# 111.net
KiCad netlist of a schematic drawn in Altium Designer
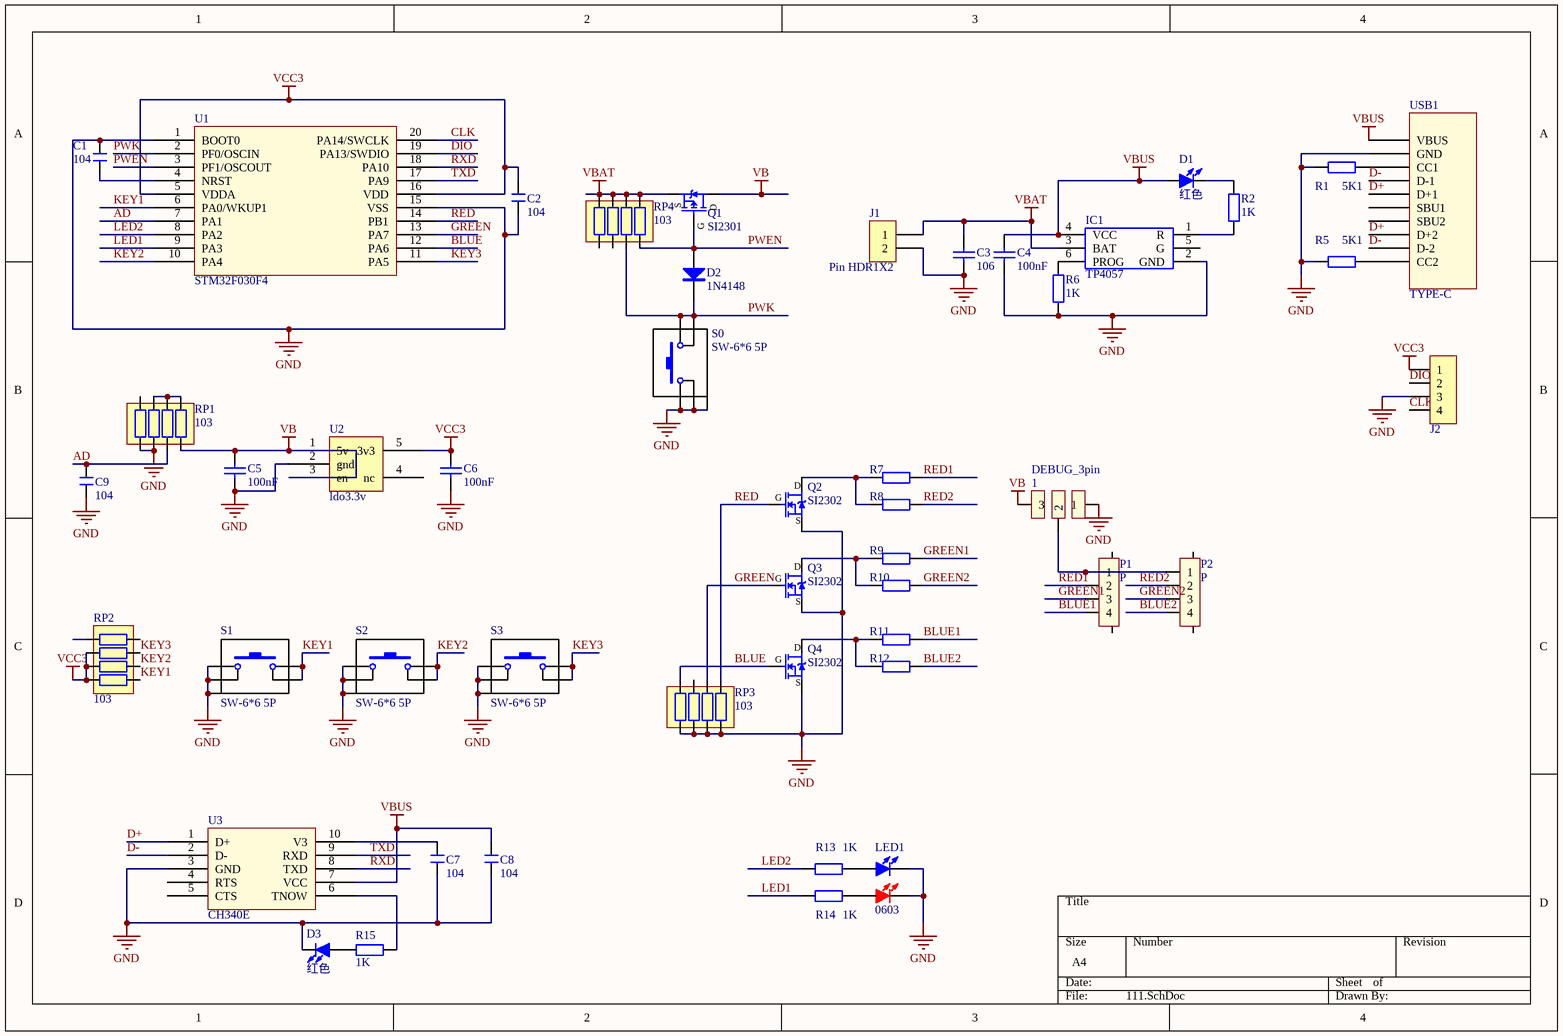
[diagram p0: 111.SchDoc]

(export (version "E")
  (design (tool "Eeschema 10.0.6"))
  (components
    (comp (ref "1") (value "DEBUG_3pin") (footprint "DEBUG_3pim") (libsource (lib "0") (part "DEBUG_3pin")))
    (comp (ref "C1")
      (value "104")
      (footprint "C 0402_M")
      (description "无极性贴片电容")
      (libsource (lib "3.1   - 电阻-电容-电感") (part "C"))
    )
    (comp (ref "C2")
      (value "104")
      (footprint "C 0402_M")
      (description "无极性贴片电容")
      (libsource (lib "3.1   - 电阻-电容-电感") (part "C"))
    )
    (comp (ref "C3")
      (value "106")
      (footprint "C-RAD-0805")
      (description "无极性电容")
      (fields (field (name "Comment") "Cap") (field (name "PUBLISHER") "Altium Limited"))
      (libsource (lib "fszhang") (part "Cap"))
    )
    (comp (ref "C4")
      (value "100nF")
      (footprint "C-RAD-0603")
      (description "无极性电容")
      (fields (field (name "Comment") "Cap") (field (name "PUBLISHER") "Altium Limited"))
      (libsource (lib "fszhang") (part "Cap"))
    )
    (comp (ref "C5")
      (value "100nF")
      (footprint "C-RAD-0603")
      (description "无极性电容")
      (fields (field (name "Comment") "Cap") (field (name "PUBLISHER") "Altium Limited"))
      (libsource (lib "fszhang") (part "Cap"))
    )
    (comp (ref "C6")
      (value "100nF")
      (footprint "C-RAD-0603")
      (description "无极性电容")
      (fields (field (name "Comment") "Cap") (field (name "PUBLISHER") "Altium Limited"))
      (libsource (lib "fszhang") (part "Cap"))
    )
    (comp (ref "C7")
      (value "104")
      (footprint "C 0402_M")
      (description "无极性贴片电容")
      (libsource (lib "3.1   - 电阻-电容-电感") (part "C"))
    )
    (comp (ref "C8")
      (value "104")
      (footprint "C 0402_M")
      (description "无极性贴片电容")
      (libsource (lib "3.1   - 电阻-电容-电感") (part "C"))
    )
    (comp (ref "C9")
      (value "104")
      (footprint "C 0402_M")
      (description "无极性贴片电容")
      (libsource (lib "3.1   - 电阻-电容-电感") (part "C"))
    )
    (comp (ref "D1")
      (value "红色")
      (footprint "LED 0603R")
      (description "贴片LED")
      (libsource (lib "9.1   - LED") (part "LED-SMD"))
    )
    (comp (ref "D2")
      (value "1N4148")
      (footprint "SOD-323")
      (description "高速开关二极管")
      (libsource (lib "8.1   - 二极管-整流桥") (part "1N4148"))
    )
    (comp (ref "D3")
      (value "红色")
      (footprint "LED 0603R")
      (description "贴片LED")
      (libsource (lib "9.1   - LED") (part "LED-SMD"))
    )
    (comp (ref "IC1") (value "TP4057") (footprint "SOT23-6M") (libsource (lib "常用") (part "TP4057")))
    (comp (ref "J1")
      (value "Pin HDR1X2")
      (footprint "Pin HDR1X2/2.54mm-S")
      (libsource (lib "排针") (part "Pin HDR1X2"))
    )
    (comp (ref "J2")
      (value "HDR-1X4")
      (footprint "HDR2.0-LI-4P")
      (description "4P接插件")
      (libsource (lib "4.5   - 接插件-脚距2.0") (part "Header 4"))
    )
    (comp (ref "LED1")
      (value "0603")
      (footprint "LED 0603-RG")
      (description "贴片双色LED")
      (libsource (lib "9.1   - LED") (part "LED-SMD-RG"))
    )
    (comp (ref "P1") (value "P") (footprint "SH1.0_4pin") (libsource (lib "0") (part "SH1.0-4")))
    (comp (ref "P2") (value "P") (footprint "SH1.0_4pin") (libsource (lib "0") (part "SH1.0-4")))
    (comp (ref "Q1")
      (value "SI2301")
      (footprint "SOT23-3N")
      (description "P沟道 20V/2.8A")
      (libsource (lib "6.1   - 场效应管-可控硅") (part "SI2301"))
    )
    (comp (ref "Q2")
      (value "SI2302")
      (footprint "SOT23-3N")
      (description "N沟道 20V/3A")
      (libsource (lib "6.1   - 场效应管-可控硅") (part "SI2302"))
    )
    (comp (ref "Q3")
      (value "SI2302")
      (footprint "SOT23-3N")
      (description "N沟道 20V/3A")
      (libsource (lib "6.1   - 场效应管-可控硅") (part "SI2302"))
    )
    (comp (ref "Q4")
      (value "SI2302")
      (footprint "SOT23-3N")
      (description "N沟道 20V/3A")
      (libsource (lib "6.1   - 场效应管-可控硅") (part "SI2302"))
    )
    (comp (ref "R1")
      (value "5K1")
      (footprint "R 0402_M")
      (description "贴片电阻")
      (libsource (lib "3.1   - 电阻-电容-电感") (part "R"))
    )
    (comp (ref "R2")
      (value "1K")
      (footprint "R 0402_M")
      (description "贴片电阻")
      (libsource (lib "3.1   - 电阻-电容-电感") (part "R"))
    )
    (comp (ref "R5")
      (value "5K1")
      (footprint "R 0402_M")
      (description "贴片电阻")
      (libsource (lib "3.1   - 电阻-电容-电感") (part "R"))
    )
    (comp (ref "R6")
      (value "1K")
      (footprint "R 0402_M")
      (description "贴片电阻")
      (libsource (lib "3.1   - 电阻-电容-电感") (part "R"))
    )
    (comp (ref "R7")
      (value "Res1")
      (footprint "0603-1")
      (description "贴片电阻")
      (fields (field (name "PUBLISHER") "Altium Limited"))
      (libsource (lib "fszhang") (part "Res1"))
    )
    (comp (ref "R8")
      (value "Res1")
      (footprint "0603-1")
      (description "贴片电阻")
      (fields (field (name "PUBLISHER") "Altium Limited"))
      (libsource (lib "fszhang") (part "Res1"))
    )
    (comp (ref "R9")
      (value "Res1")
      (footprint "0603-1")
      (description "贴片电阻")
      (fields (field (name "PUBLISHER") "Altium Limited"))
      (libsource (lib "fszhang") (part "Res1"))
    )
    (comp (ref "R10")
      (value "Res1")
      (footprint "0603-1")
      (description "贴片电阻")
      (fields (field (name "PUBLISHER") "Altium Limited"))
      (libsource (lib "fszhang") (part "Res1"))
    )
    (comp (ref "R11")
      (value "Res1")
      (footprint "0603-1")
      (description "贴片电阻")
      (fields (field (name "PUBLISHER") "Altium Limited"))
      (libsource (lib "fszhang") (part "Res1"))
    )
    (comp (ref "R12")
      (value "Res1")
      (footprint "0603-1")
      (description "贴片电阻")
      (fields (field (name "PUBLISHER") "Altium Limited"))
      (libsource (lib "fszhang") (part "Res1"))
    )
    (comp (ref "R13")
      (value "1K")
      (footprint "R 0402_M")
      (description "贴片电阻")
      (libsource (lib "3.1   - 电阻-电容-电感") (part "R"))
    )
    (comp (ref "R14")
      (value "1K")
      (footprint "R 0402_M")
      (description "贴片电阻")
      (libsource (lib "3.1   - 电阻-电容-电感") (part "R"))
    )
    (comp (ref "R15")
      (value "1K")
      (footprint "R 0402_M")
      (description "贴片电阻")
      (libsource (lib "3.1   - 电阻-电容-电感") (part "R"))
    )
    (comp (ref "RP1")
      (value "103")
      (footprint "RCA-8P4R-0402")
      (description "贴片网络排阻")
      (libsource (lib "3.1   - 电阻-电容-电感") (part "R-8P4R"))
    )
    (comp (ref "RP2")
      (value "103")
      (footprint "RCA-8P4R-0402")
      (description "贴片网络排阻")
      (libsource (lib "") (part "R-8P4R_1"))
    )
    (comp (ref "RP3")
      (value "103")
      (footprint "RCA-8P4R-0402")
      (description "贴片网络排阻")
      (libsource (lib "3.1   - 电阻-电容-电感") (part "R-8P4R"))
    )
    (comp (ref "RP4")
      (value "103")
      (footprint "RCA-8P4R-0402")
      (description "贴片网络排阻")
      (libsource (lib "3.1   - 电阻-电容-电感") (part "R-8P4R"))
    )
    (comp (ref "S0")
      (value "SW-6*6 5P")
      (footprint "SW6*6")
      (description "微动开关")
      (fields (field (name "PUBLISHER") "Altium Limited"))
      (libsource (lib "fszhang") (part "SW-6*6 5P"))
    )
    (comp (ref "S1")
      (value "SW-6*6 5P")
      (footprint "SW6*6")
      (description "微动开关")
      (fields (field (name "PUBLISHER") "Altium Limited"))
      (libsource (lib "fszhang") (part "SW-6*6 5P"))
    )
    (comp (ref "S2")
      (value "SW-6*6 5P")
      (footprint "SW6*6")
      (description "微动开关")
      (fields (field (name "PUBLISHER") "Altium Limited"))
      (libsource (lib "fszhang") (part "SW-6*6 5P"))
    )
    (comp (ref "S3")
      (value "SW-6*6 5P")
      (footprint "SW6*6")
      (description "微动开关")
      (fields (field (name "PUBLISHER") "Altium Limited"))
      (libsource (lib "fszhang") (part "SW-6*6 5P"))
    )
    (comp (ref "U1")
      (value "STM32F030F4")
      (footprint "TSSOP20")
      (libsource (lib "fszhang") (part "STM32F030F4"))
    )
    (comp (ref "U2") (value "ldo3.3v") (footprint "SOT23-5") (libsource (lib "3.3ldo") (part "Component_1")))
    (comp (ref "U3") (value "CH340E") (footprint "MSOP10_M") (libsource (lib "1") (part "CH340E")))
    (comp (ref "USB1") (value "TYPE-C") (footprint "TYPE-C") (libsource (lib "1") (part "USB-C")))
  )
  (nets
    (net (code "1") (name "/AD") (class "Default")
      (node (ref "C9") (pin "2") (pinfunction "2_2") (pintype "passive"))
      (node (ref "RP1") (pin "3") (pinfunction "3_3") (pintype "passive"))
      (node (ref "U1") (pin "7") (pinfunction "PA1_7") (pintype "passive"))
    )
    (net (code "2") (name "/BLUE") (class "Default")
      (node (ref "Q4") (pin "1") (pinfunction "G_1") (pintype "passive"))
      (node (ref "RP3") (pin "8") (pinfunction "8_8") (pintype "passive"))
      (node (ref "U1") (pin "12") (pinfunction "PA6_12") (pintype "passive"))
    )
    (net (code "3") (name "/BLUE1") (class "Default")
      (node (ref "P1") (pin "4") (pinfunction "4_4") (pintype "passive"))
      (node (ref "R11") (pin "2") (pinfunction "2_2") (pintype "passive"))
    )
    (net (code "4") (name "/BLUE2") (class "Default")
      (node (ref "P2") (pin "4") (pinfunction "4_4") (pintype "passive"))
      (node (ref "R12") (pin "2") (pinfunction "2_2") (pintype "passive"))
    )
    (net (code "5") (name "/CLK") (class "Default")
      (node (ref "J2") (pin "4") (pinfunction "4_4") (pintype "passive"))
      (node (ref "U1") (pin "20") (pinfunction "PA14/SWCLK_20") (pintype "passive"))
    )
    (net (code "6") (name "/D+") (class "Default")
      (node (ref "U3") (pin "1") (pinfunction "D+_1") (pintype "passive"))
      (node (ref "USB1") (pin "D+1") (pinfunction "D+1_D+1") (pintype "passive"))
      (node (ref "USB1") (pin "D+2") (pinfunction "D+2_D+2") (pintype "passive"))
    )
    (net (code "7") (name "/D-") (class "Default")
      (node (ref "U3") (pin "2") (pinfunction "D-_2") (pintype "passive"))
      (node (ref "USB1") (pin "D-1") (pinfunction "D-1_D-1") (pintype "passive"))
      (node (ref "USB1") (pin "D-2") (pinfunction "D-2_D-2") (pintype "passive"))
    )
    (net (code "8") (name "/DIO") (class "Default")
      (node (ref "J2") (pin "2") (pinfunction "2_2") (pintype "passive"))
      (node (ref "U1") (pin "19") (pinfunction "PA13/SWDIO_19") (pintype "passive"))
    )
    (net (code "9") (name "/GREEN") (class "Default")
      (node (ref "Q3") (pin "1") (pinfunction "G_1") (pintype "passive"))
      (node (ref "RP3") (pin "6") (pinfunction "6_6") (pintype "passive"))
      (node (ref "U1") (pin "13") (pinfunction "PA7_13") (pintype "passive"))
    )
    (net (code "10") (name "/GREEN1") (class "Default")
      (node (ref "P1") (pin "3") (pinfunction "3_3") (pintype "passive"))
      (node (ref "R9") (pin "2") (pinfunction "2_2") (pintype "passive"))
    )
    (net (code "11") (name "/GREEN2") (class "Default")
      (node (ref "P2") (pin "3") (pinfunction "3_3") (pintype "passive"))
      (node (ref "R10") (pin "2") (pinfunction "2_2") (pintype "passive"))
    )
    (net (code "12") (name "/KEY1") (class "Default")
      (node (ref "RP2") (pin "1") (pinfunction "1_1") (pintype "passive"))
      (node (ref "S1") (pin "2") (pinfunction "2_2") (pintype "passive"))
      (node (ref "S1") (pin "3") (pinfunction "3_3") (pintype "passive"))
      (node (ref "U1") (pin "6") (pinfunction "PA0/WKUP1_6") (pintype "passive"))
    )
    (net (code "13") (name "/KEY2") (class "Default")
      (node (ref "RP2") (pin "2") (pinfunction "2_2") (pintype "passive"))
      (node (ref "S2") (pin "2") (pinfunction "2_2") (pintype "passive"))
      (node (ref "S2") (pin "3") (pinfunction "3_3") (pintype "passive"))
      (node (ref "U1") (pin "10") (pinfunction "PA4_10") (pintype "passive"))
    )
    (net (code "14") (name "/KEY3") (class "Default")
      (node (ref "RP2") (pin "3") (pinfunction "3_3") (pintype "passive"))
      (node (ref "S3") (pin "2") (pinfunction "2_2") (pintype "passive"))
      (node (ref "S3") (pin "3") (pinfunction "3_3") (pintype "passive"))
      (node (ref "U1") (pin "11") (pinfunction "PA5_11") (pintype "passive"))
    )
    (net (code "15") (name "/LED1") (class "Default")
      (node (ref "R14") (pin "1") (pinfunction "1_1") (pintype "passive"))
      (node (ref "U1") (pin "9") (pinfunction "PA3_9") (pintype "passive"))
    )
    (net (code "16") (name "/LED2") (class "Default")
      (node (ref "R13") (pin "1") (pinfunction "1_1") (pintype "passive"))
      (node (ref "U1") (pin "8") (pinfunction "PA2_8") (pintype "passive"))
    )
    (net (code "17") (name "/PWEN") (class "Default")
      (node (ref "D2") (pin "A") (pinfunction "A_A") (pintype "passive"))
      (node (ref "Q1") (pin "1") (pinfunction "G_1") (pintype "passive"))
      (node (ref "RP4") (pin "4") (pinfunction "4_4") (pintype "passive"))
      (node (ref "U1") (pin "3") (pinfunction "PF1/OSCOUT_3") (pintype "passive"))
    )
    (net (code "18") (name "/PWK") (class "Default")
      (node (ref "D2") (pin "K") (pinfunction "K_K") (pintype "passive"))
      (node (ref "RP4") (pin "3") (pinfunction "3_3") (pintype "passive"))
      (node (ref "S0") (pin "2") (pinfunction "2_2") (pintype "passive"))
      (node (ref "S0") (pin "3") (pinfunction "3_3") (pintype "passive"))
      (node (ref "U1") (pin "2") (pinfunction "PF0/OSCIN_2") (pintype "passive"))
    )
    (net (code "19") (name "/RED") (class "Default")
      (node (ref "Q2") (pin "1") (pinfunction "G_1") (pintype "passive"))
      (node (ref "RP3") (pin "5") (pinfunction "5_5") (pintype "passive"))
      (node (ref "U1") (pin "14") (pinfunction "PB1_14") (pintype "passive"))
    )
    (net (code "20") (name "/RED1") (class "Default")
      (node (ref "P1") (pin "2") (pinfunction "2_2") (pintype "passive"))
      (node (ref "R7") (pin "2") (pinfunction "2_2") (pintype "passive"))
    )
    (net (code "21") (name "/RED2") (class "Default")
      (node (ref "P2") (pin "2") (pinfunction "2_2") (pintype "passive"))
      (node (ref "R8") (pin "2") (pinfunction "2_2") (pintype "passive"))
    )
    (net (code "22") (name "/RXD") (class "Default")
      (node (ref "U1") (pin "18") (pinfunction "PA10_18") (pintype "passive"))
      (node (ref "U3") (pin "8") (pinfunction "TXD_8") (pintype "passive"))
    )
    (net (code "23") (name "/TXD") (class "Default")
      (node (ref "U1") (pin "17") (pinfunction "PA9_17") (pintype "passive"))
      (node (ref "U3") (pin "9") (pinfunction "RXD_9") (pintype "passive"))
    )
    (net (code "24") (name "GND") (class "Default")
      (node (ref "1") (pin "1") (pinfunction "1_1") (pintype "passive"))
      (node (ref "C1") (pin "2") (pinfunction "2_2") (pintype "passive"))
      (node (ref "C2") (pin "1") (pinfunction "1_1") (pintype "passive"))
      (node (ref "C3") (pin "1") (pinfunction "1_1") (pintype "passive"))
      (node (ref "C4") (pin "1") (pinfunction "1_1") (pintype "passive"))
      (node (ref "C5") (pin "1") (pinfunction "1_1") (pintype "passive"))
      (node (ref "C6") (pin "1") (pinfunction "1_1") (pintype "passive"))
      (node (ref "C7") (pin "1") (pinfunction "1_1") (pintype "passive"))
      (node (ref "C8") (pin "1") (pinfunction "1_1") (pintype "passive"))
      (node (ref "C9") (pin "1") (pinfunction "1_1") (pintype "passive"))
      (node (ref "D3") (pin "2") (pinfunction "K_2") (pintype "passive"))
      (node (ref "IC1") (pin "2") (pinfunction "GND_2") (pintype "passive"))
      (node (ref "J1") (pin "2") (pinfunction "2_2") (pintype "passive"))
      (node (ref "J2") (pin "3") (pinfunction "3_3") (pintype "passive"))
      (node (ref "LED1") (pin "3") (pinfunction "3_3") (pintype "passive"))
      (node (ref "LED1") (pin "4") (pinfunction "4_4") (pintype "passive"))
      (node (ref "Q2") (pin "2") (pinfunction "S_2") (pintype "passive"))
      (node (ref "Q3") (pin "2") (pinfunction "S_2") (pintype "passive"))
      (node (ref "Q4") (pin "2") (pinfunction "S_2") (pintype "passive"))
      (node (ref "R1") (pin "2") (pinfunction "2_2") (pintype "passive"))
      (node (ref "R5") (pin "2") (pinfunction "2_2") (pintype "passive"))
      (node (ref "R6") (pin "1") (pinfunction "1_1") (pintype "passive"))
      (node (ref "RP1") (pin "1") (pinfunction "1_1") (pintype "passive"))
      (node (ref "RP1") (pin "2") (pinfunction "2_2") (pintype "passive"))
      (node (ref "RP3") (pin "1") (pinfunction "1_1") (pintype "passive"))
      (node (ref "RP3") (pin "2") (pinfunction "2_2") (pintype "passive"))
      (node (ref "RP3") (pin "3") (pinfunction "3_3") (pintype "passive"))
      (node (ref "RP3") (pin "4") (pinfunction "4_4") (pintype "passive"))
      (node (ref "S0") (pin "1") (pinfunction "1_1") (pintype "passive"))
      (node (ref "S0") (pin "4") (pinfunction "4_4") (pintype "passive"))
      (node (ref "S0") (pin "5") (pinfunction "5_5") (pintype "passive"))
      (node (ref "S1") (pin "1") (pinfunction "1_1") (pintype "passive"))
      (node (ref "S1") (pin "4") (pinfunction "4_4") (pintype "passive"))
      (node (ref "S1") (pin "5") (pinfunction "5_5") (pintype "passive"))
      (node (ref "S2") (pin "1") (pinfunction "1_1") (pintype "passive"))
      (node (ref "S2") (pin "4") (pinfunction "4_4") (pintype "passive"))
      (node (ref "S2") (pin "5") (pinfunction "5_5") (pintype "passive"))
      (node (ref "S3") (pin "1") (pinfunction "1_1") (pintype "passive"))
      (node (ref "S3") (pin "4") (pinfunction "4_4") (pintype "passive"))
      (node (ref "S3") (pin "5") (pinfunction "5_5") (pintype "passive"))
      (node (ref "U1") (pin "1") (pinfunction "BOOT0_1") (pintype "passive"))
      (node (ref "U1") (pin "15") (pinfunction "VSS_15") (pintype "passive"))
      (node (ref "U2") (pin "2") (pinfunction "gnd_2") (pintype "passive"))
      (node (ref "U3") (pin "3") (pinfunction "GND_3") (pintype "passive"))
      (node (ref "USB1") (pin "GND") (pinfunction "GND_GND") (pintype "passive"))
    )
    (net (code "25") (name "Net-(1-Pad2)") (class "Default")
      (node (ref "1") (pin "2") (pinfunction "2_2") (pintype "passive"))
      (node (ref "P1") (pin "1") (pinfunction "1_1") (pintype "passive"))
      (node (ref "P2") (pin "1") (pinfunction "1_1") (pintype "passive"))
    )
    (net (code "26") (name "Net-(D1-K)") (class "Default")
      (node (ref "D1") (pin "2") (pinfunction "K_2") (pintype "passive"))
      (node (ref "R2") (pin "2") (pinfunction "2_2") (pintype "passive"))
    )
    (net (code "27") (name "Net-(D3-A)") (class "Default")
      (node (ref "D3") (pin "1") (pinfunction "A_1") (pintype "passive"))
      (node (ref "R15") (pin "2") (pinfunction "2_2") (pintype "passive"))
    )
    (net (code "28") (name "Net-(IC1-PROG)") (class "Default")
      (node (ref "IC1") (pin "6") (pinfunction "PROG_6") (pintype "passive"))
      (node (ref "R6") (pin "2") (pinfunction "2_2") (pintype "passive"))
    )
    (net (code "29") (name "Net-(IC1-R)") (class "Default")
      (node (ref "IC1") (pin "1") (pinfunction "R_1") (pintype "passive"))
      (node (ref "R2") (pin "1") (pinfunction "1_1") (pintype "passive"))
    )
    (net (code "30") (name "Net-(LED1-1-Pad2)") (class "Default")
      (node (ref "LED1") (pin "2") (pinfunction "1_2") (pintype "passive"))
      (node (ref "R14") (pin "2") (pinfunction "2_2") (pintype "passive"))
    )
    (net (code "31") (name "Net-(LED1-Pad1)") (class "Default")
      (node (ref "LED1") (pin "1") (pinfunction "1_1") (pintype "passive"))
      (node (ref "R13") (pin "2") (pinfunction "2_2") (pintype "passive"))
    )
    (net (code "32") (name "Net-(Q2-D)") (class "Default")
      (node (ref "Q2") (pin "3") (pinfunction "D_3") (pintype "passive"))
      (node (ref "R7") (pin "1") (pinfunction "1_1") (pintype "passive"))
      (node (ref "R8") (pin "1") (pinfunction "1_1") (pintype "passive"))
    )
    (net (code "33") (name "Net-(Q3-D)") (class "Default")
      (node (ref "Q3") (pin "3") (pinfunction "D_3") (pintype "passive"))
      (node (ref "R10") (pin "1") (pinfunction "1_1") (pintype "passive"))
      (node (ref "R9") (pin "1") (pinfunction "1_1") (pintype "passive"))
    )
    (net (code "34") (name "Net-(Q4-D)") (class "Default")
      (node (ref "Q4") (pin "3") (pinfunction "D_3") (pintype "passive"))
      (node (ref "R11") (pin "1") (pinfunction "1_1") (pintype "passive"))
      (node (ref "R12") (pin "1") (pinfunction "1_1") (pintype "passive"))
    )
    (net (code "35") (name "Net-(R1-Pad1)") (class "Default")
      (node (ref "R1") (pin "1") (pinfunction "1_1") (pintype "passive"))
      (node (ref "USB1") (pin "CC1") (pinfunction "CC1_CC1") (pintype "passive"))
    )
    (net (code "36") (name "Net-(R5-Pad1)") (class "Default")
      (node (ref "R5") (pin "1") (pinfunction "1_1") (pintype "passive"))
      (node (ref "USB1") (pin "CC2") (pinfunction "CC2_CC2") (pintype "passive"))
    )
    (net (code "37") (name "Net-(RP1-Pad5)") (class "Default")
      (node (ref "RP1") (pin "5") (pinfunction "5_5") (pintype "passive"))
      (node (ref "RP1") (pin "6") (pinfunction "6_6") (pintype "passive"))
      (node (ref "RP1") (pin "7") (pinfunction "7_7") (pintype "passive"))
    )
    (net (code "38") (name "Net-(U1-NRST)") (class "Default")
      (node (ref "C1") (pin "1") (pinfunction "1_1") (pintype "passive"))
      (node (ref "U1") (pin "4") (pinfunction "NRST_4") (pintype "passive"))
    )
    (net (code "39") (name "Net-(U3-TNOW)") (class "Default")
      (node (ref "R15") (pin "1") (pinfunction "1_1") (pintype "passive"))
      (node (ref "U3") (pin "6") (pinfunction "TNOW_6") (pintype "passive"))
    )
    (net (code "40") (name "Net-(U3-V3)") (class "Default")
      (node (ref "C7") (pin "2") (pinfunction "2_2") (pintype "passive"))
      (node (ref "U3") (pin "10") (pinfunction "V3_10") (pintype "passive"))
    )
    (net (code "41") (name "VB") (class "Default")
      (node (ref "1") (pin "3") (pinfunction "3_3") (pintype "passive"))
      (node (ref "C5") (pin "2") (pinfunction "2_2") (pintype "passive"))
      (node (ref "Q1") (pin "3") (pinfunction "D_3") (pintype "passive"))
      (node (ref "RP1") (pin "4") (pinfunction "4_4") (pintype "passive"))
      (node (ref "U2") (pin "1") (pinfunction "5v_1") (pintype "passive"))
      (node (ref "U2") (pin "3") (pinfunction "en_3") (pintype "passive"))
    )
    (net (code "42") (name "VBAT") (class "Default")
      (node (ref "C3") (pin "2") (pinfunction "2_2") (pintype "passive"))
      (node (ref "IC1") (pin "3") (pinfunction "BAT_3") (pintype "passive"))
      (node (ref "J1") (pin "1") (pinfunction "1_1") (pintype "passive"))
      (node (ref "Q1") (pin "2") (pinfunction "S_2") (pintype "passive"))
      (node (ref "RP4") (pin "5") (pinfunction "5_5") (pintype "passive"))
      (node (ref "RP4") (pin "6") (pinfunction "6_6") (pintype "passive"))
      (node (ref "RP4") (pin "7") (pinfunction "7_7") (pintype "passive"))
      (node (ref "RP4") (pin "8") (pinfunction "8_8") (pintype "passive"))
    )
    (net (code "43") (name "VBUS") (class "Default")
      (node (ref "C4") (pin "2") (pinfunction "2_2") (pintype "passive"))
      (node (ref "C8") (pin "2") (pinfunction "2_2") (pintype "passive"))
      (node (ref "D1") (pin "1") (pinfunction "A_1") (pintype "passive"))
      (node (ref "IC1") (pin "4") (pinfunction "VCC_4") (pintype "passive"))
      (node (ref "U3") (pin "7") (pinfunction "VCC_7") (pintype "passive"))
      (node (ref "USB1") (pin "VBUS") (pinfunction "VBUS_VBUS") (pintype "passive"))
    )
    (net (code "44") (name "VCC3") (class "Default")
      (node (ref "C2") (pin "2") (pinfunction "2_2") (pintype "passive"))
      (node (ref "C6") (pin "2") (pinfunction "2_2") (pintype "passive"))
      (node (ref "J2") (pin "1") (pinfunction "1_1") (pintype "passive"))
      (node (ref "RP2") (pin "6") (pinfunction "6_6") (pintype "passive"))
      (node (ref "RP2") (pin "7") (pinfunction "7_7") (pintype "passive"))
      (node (ref "RP2") (pin "8") (pinfunction "8_8") (pintype "passive"))
      (node (ref "U1") (pin "16") (pinfunction "VDD_16") (pintype "passive"))
      (node (ref "U1") (pin "5") (pinfunction "VDDA_5") (pintype "passive"))
      (node (ref "U2") (pin "5") (pinfunction "3v3_5") (pintype "passive"))
    )
    (net (code "45") (name "unconnected-(IC1-G-Pad5)") (class "Default")
      (node (ref "IC1") (pin "5") (pinfunction "G_5") (pintype "passive"))
    )
    (net (code "46") (name "unconnected-(P1-Pad0)") (class "Default")
      (node (ref "P1") (pin "0") (pinfunction "0_0") (pintype "passive"))
    )
    (net (code "47") (name "unconnected-(P1-Pad0)_1") (class "Default")
      (node (ref "P1") (pin "0") (pinfunction "0_0") (pintype "passive"))
    )
    (net (code "48") (name "unconnected-(P2-Pad0)") (class "Default")
      (node (ref "P2") (pin "0") (pinfunction "0_0") (pintype "passive"))
    )
    (net (code "49") (name "unconnected-(P2-Pad0)_1") (class "Default")
      (node (ref "P2") (pin "0") (pinfunction "0_0") (pintype "passive"))
    )
    (net (code "50") (name "unconnected-(RP1-Pad8)") (class "Default")
      (node (ref "RP1") (pin "8") (pinfunction "8_8") (pintype "passive"))
    )
    (net (code "51") (name "unconnected-(RP2-Pad4)") (class "Default")
      (node (ref "RP2") (pin "4") (pinfunction "4_4") (pintype "passive"))
    )
    (net (code "52") (name "unconnected-(RP2-Pad5)") (class "Default")
      (node (ref "RP2") (pin "5") (pinfunction "5_5") (pintype "passive"))
    )
    (net (code "53") (name "unconnected-(RP3-Pad7)") (class "Default")
      (node (ref "RP3") (pin "7") (pinfunction "7_7") (pintype "passive"))
    )
    (net (code "54") (name "unconnected-(RP4-Pad1)") (class "Default")
      (node (ref "RP4") (pin "1") (pinfunction "1_1") (pintype "passive"))
    )
    (net (code "55") (name "unconnected-(RP4-Pad2)") (class "Default")
      (node (ref "RP4") (pin "2") (pinfunction "2_2") (pintype "passive"))
    )
    (net (code "56") (name "unconnected-(U2-nc-Pad4)") (class "Default")
      (node (ref "U2") (pin "4") (pinfunction "nc_4") (pintype "passive"))
    )
    (net (code "57") (name "unconnected-(U3-CTS-Pad5)") (class "Default")
      (node (ref "U3") (pin "5") (pinfunction "CTS_5") (pintype "passive"))
    )
    (net (code "58") (name "unconnected-(U3-RTS-Pad4)") (class "Default")
      (node (ref "U3") (pin "4") (pinfunction "RTS_4") (pintype "passive"))
    )
    (net (code "59") (name "unconnected-(USB1-PadSBU1)") (class "Default")
      (node (ref "USB1") (pin "SBU1") (pinfunction "SBU1_SBU1") (pintype "passive"))
    )
    (net (code "60") (name "unconnected-(USB1-PadSBU2)") (class "Default")
      (node (ref "USB1") (pin "SBU2") (pinfunction "SBU2_SBU2") (pintype "passive"))
    )
  )
)
